# hi-link-ac-to-low-dc-general.net
KiCad netlist of a schematic drawn in EAGLE
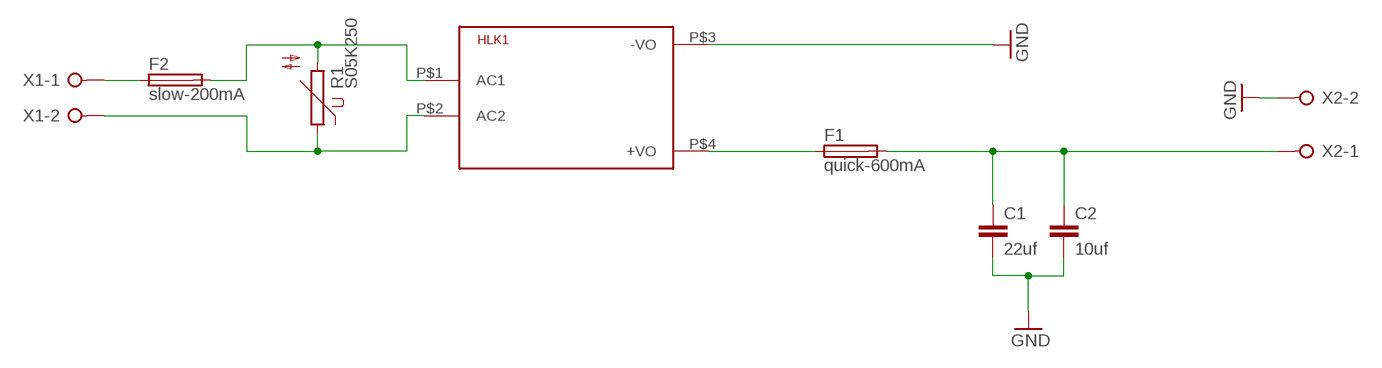
[diagram p0: schematic, sheet 1]

(export (version "E")
  (design (tool "Eeschema 10.0.6"))
  (components
    (comp (ref "C1")
      (value "22uf")
      (footprint "eagle-import:C1206")
      (libsource (lib "eagle-import") (part "C-EUC1206"))
    )
    (comp (ref "C2")
      (value "10uf")
      (footprint "eagle-import:C1206")
      (libsource (lib "eagle-import") (part "C-EUC1206"))
    )
    (comp (ref "F1")
      (value "quick-600mA")
      (footprint "eagle-import:SH22,5")
      (fields (field (name "MF") "SCHURTER") (field (name "MPN") "0031.8201"))
      (libsource (lib "eagle-import") (part "SH22,5"))
    )
    (comp (ref "F2")
      (value "slow-200mA")
      (footprint "eagle-import:SH22,5")
      (fields (field (name "MF") "SCHURTER") (field (name "MPN") "0031.8201"))
      (libsource (lib "eagle-import") (part "SH22,5"))
    )
    (comp (ref "HLK1")
      (value "HLK-PM013W")
      (footprint "eagle-import:HLK-PM01")
      (libsource (lib "eagle-import") (part "HLK-PM013W"))
    )
    (comp (ref "R1")
      (value "S05K250")
      (footprint "eagle-import:S05K250")
      (libsource (lib "eagle-import") (part "S05K250"))
    )
    (comp (ref "X1")
      (value "W237-02P")
      (footprint "eagle-import:W237-132")
      (libsource (lib "eagle-import") (part "W237-02P"))
    )
    (comp (ref "X2")
      (value "W237-02P")
      (footprint "eagle-import:W237-132")
      (libsource (lib "eagle-import") (part "W237-02P"))
    )
  )
  (nets
    (net (code "1") (name "GND") (class "Default")
      (node (ref "C1") (pin "2") (pinfunction "2_2") (pintype "passive"))
      (node (ref "C2") (pin "2") (pinfunction "2_2") (pintype "passive"))
      (node (ref "HLK1") (pin "P$3") (pinfunction "-VO_P$3") (pintype "bidirectional"))
      (node (ref "X2") (pin "2") (pinfunction "KL_2") (pintype "passive"))
    )
    (net (code "2") (name "Net-(HLK1-+VO)") (class "Default")
      (node (ref "F1") (pin "1") (pinfunction "1_1") (pintype "passive"))
      (node (ref "HLK1") (pin "P$4") (pinfunction "+VO_P$4") (pintype "bidirectional"))
    )
    (net (code "3") (name "Net-(HLK1-AC1)") (class "Default")
      (node (ref "F2") (pin "2") (pinfunction "2_2") (pintype "passive"))
      (node (ref "HLK1") (pin "P$1") (pinfunction "AC1_P$1") (pintype "bidirectional"))
      (node (ref "R1") (pin "2") (pinfunction "2_2") (pintype "passive"))
    )
    (net (code "4") (name "Net-(HLK1-AC2)") (class "Default")
      (node (ref "HLK1") (pin "P$2") (pinfunction "AC2_P$2") (pintype "bidirectional"))
      (node (ref "R1") (pin "1") (pinfunction "1_1") (pintype "passive"))
      (node (ref "X1") (pin "2") (pinfunction "KL_2") (pintype "passive"))
    )
    (net (code "5") (name "Net-(X1A-KL)") (class "Default")
      (node (ref "F2") (pin "1") (pinfunction "1_1") (pintype "passive"))
      (node (ref "X1") (pin "1") (pinfunction "KL_1") (pintype "passive"))
    )
    (net (code "6") (name "Net-(X2A-KL)") (class "Default")
      (node (ref "C1") (pin "1") (pinfunction "1_1") (pintype "passive"))
      (node (ref "C2") (pin "1") (pinfunction "1_1") (pintype "passive"))
      (node (ref "F1") (pin "2") (pinfunction "2_2") (pintype "passive"))
      (node (ref "X2") (pin "1") (pinfunction "KL_1") (pintype "passive"))
    )
  )
)
